# SCH_ESP8266_2025-01-11.net
KiCad netlist of a schematic drawn in EasyEDA
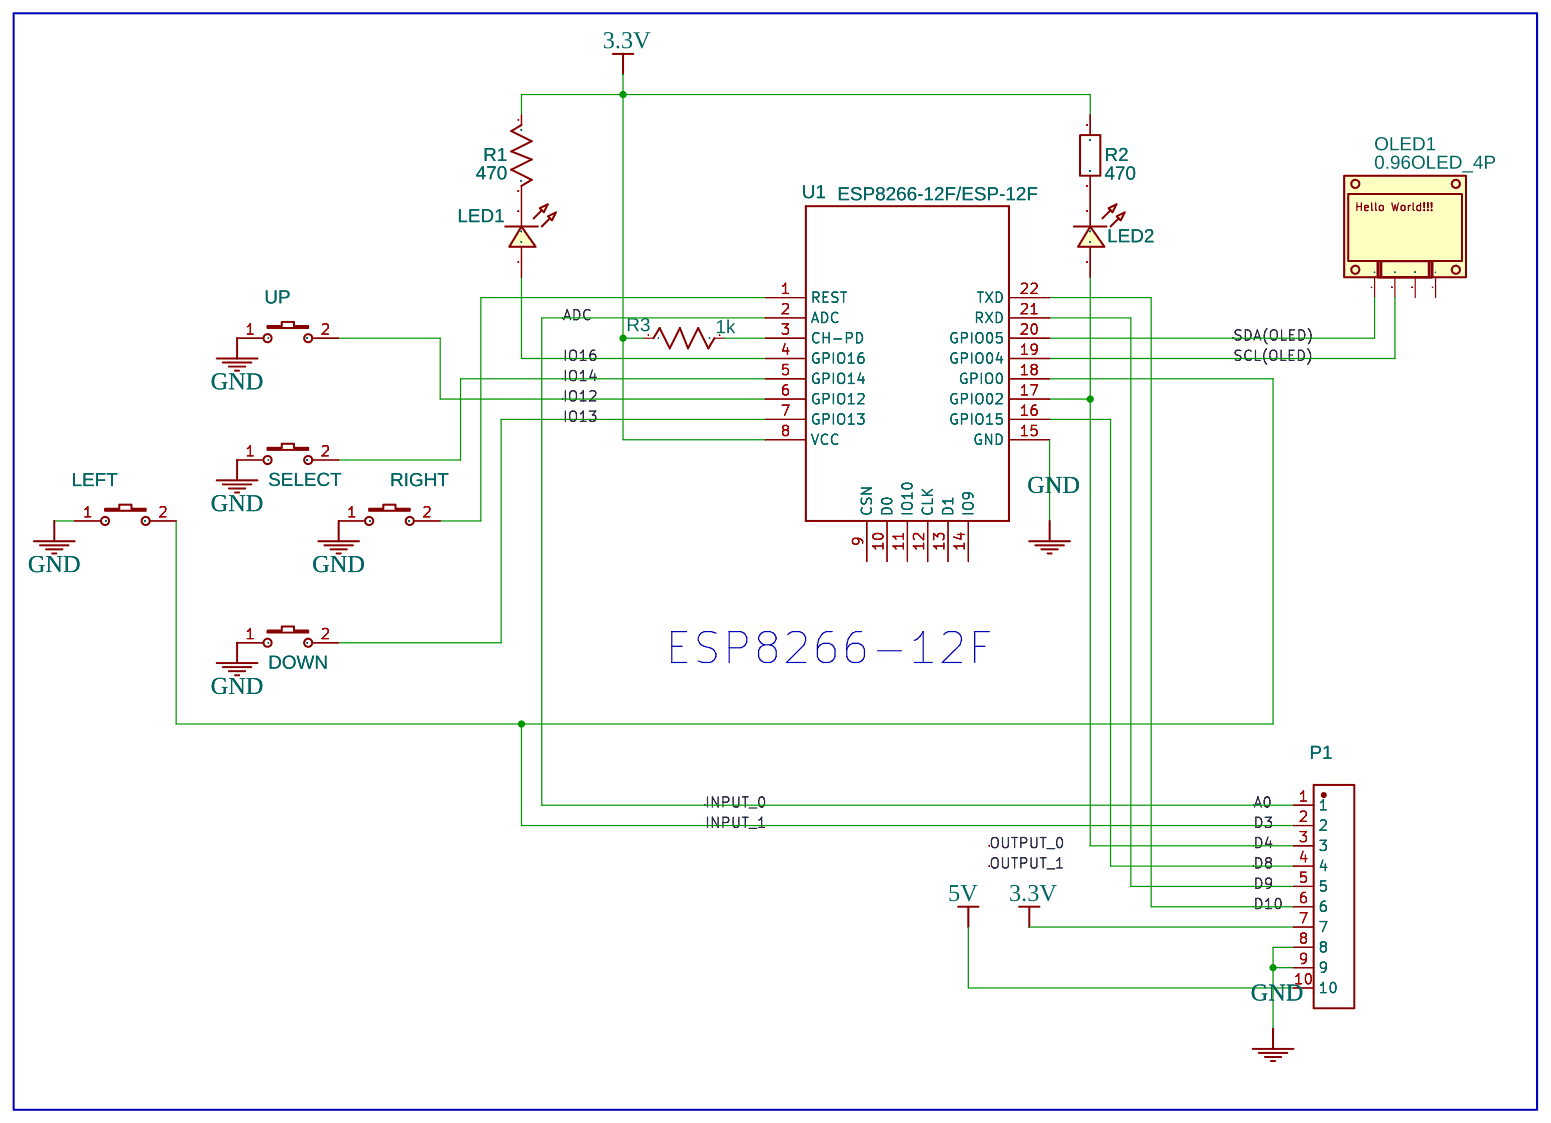
[diagram p0: ESP8266]
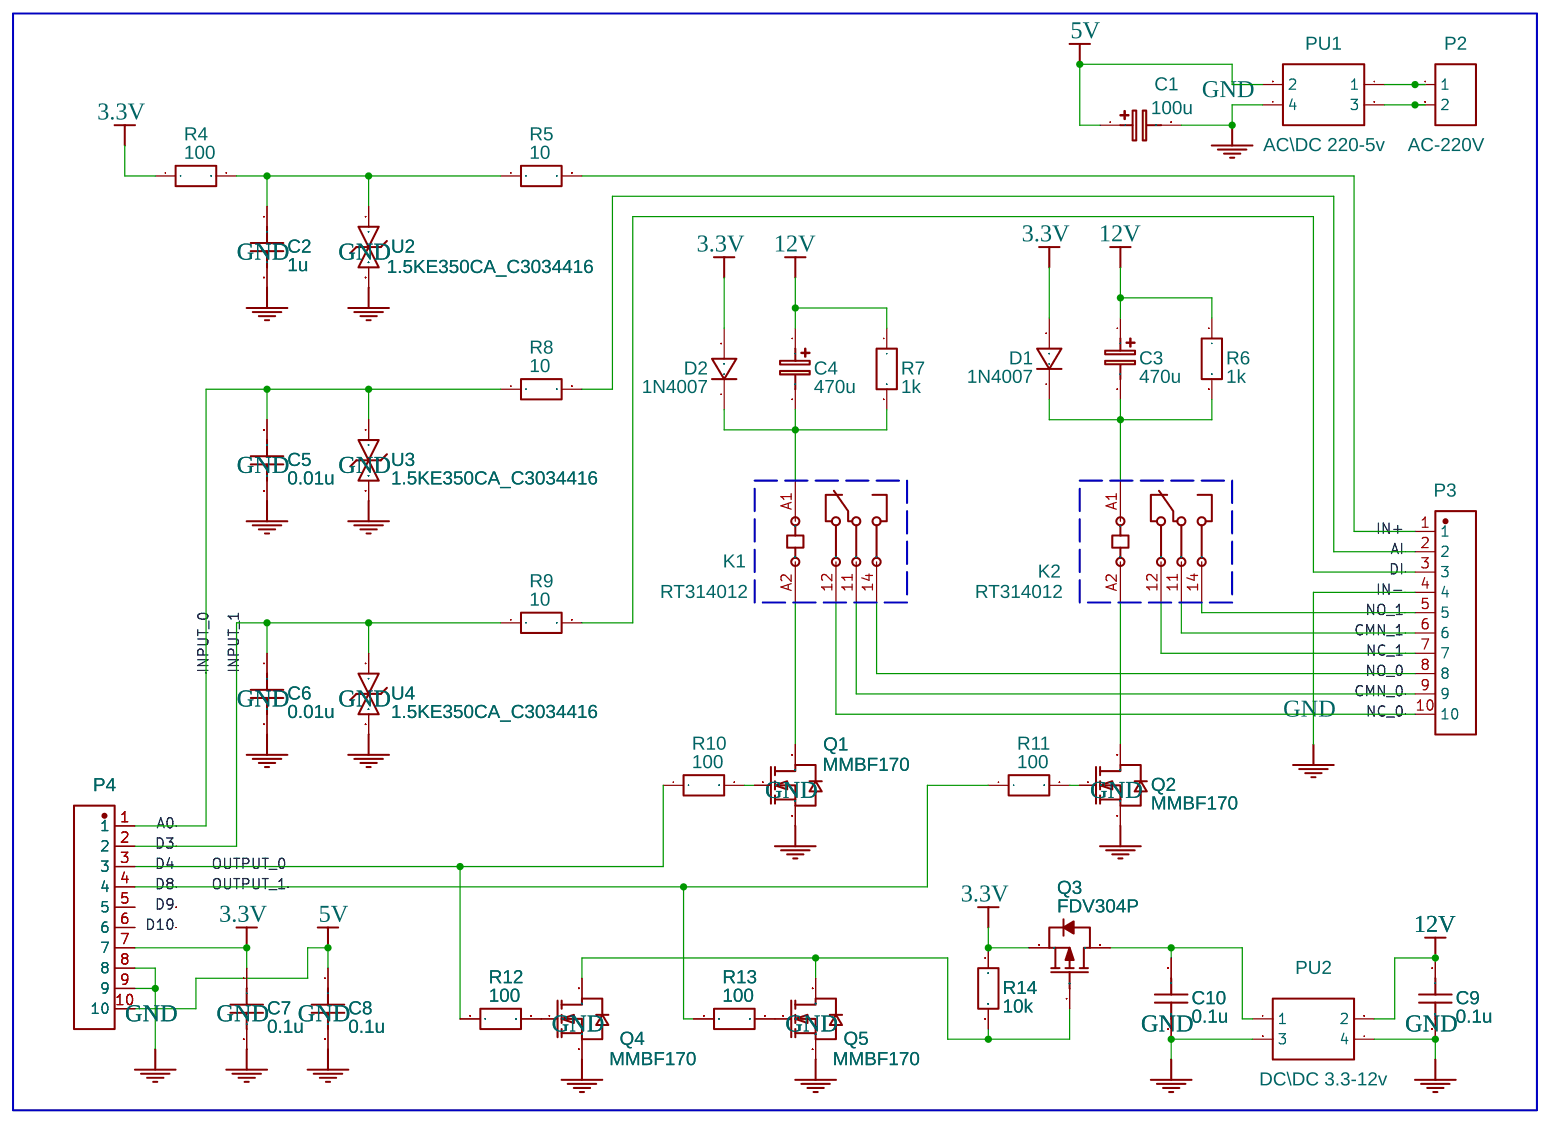
[diagram p1: Peripheral]

(export (version "E")
  (design (tool "Eeschema 10.0.6"))
  (components
    (comp (ref "DOWN")
      (value "K2-3.6×6.1_SMD")
      (fields (field (name "Manufacturer Part") "K2-1107ST-A4SW-06"))
      (libsource (lib "") (part "K2-3.6×6.1_SMD_3"))
    )
    (comp (ref "LED1")
      (value "LED-0603_R")
      (fields
        (field (name "Manufacturer Part") "19-217/R6C-AL1M2VY/3T")
        (field (name "Manufacturer") "EVERLIGHT(台湾亿光)")
      )
      (libsource (lib "") (part "LED-0603_R"))
    )
    (comp (ref "LED2")
      (value "LED-0603_R")
      (fields
        (field (name "Manufacturer Part") "19-217/R6C-AL1M2VY/3T")
        (field (name "Manufacturer") "EVERLIGHT(台湾亿光)")
      )
      (libsource (lib "") (part "LED-0603_R"))
    )
    (comp (ref "LEFT")
      (value "K2-3.6×6.1_SMD")
      (fields (field (name "Manufacturer Part") "K2-1107ST-A4SW-06"))
      (libsource (lib "") (part "K2-3.6×6.1_SMD_1"))
    )
    (comp (ref "OLED1") (value "0.96OLED_4P") (libsource (lib "") (part "0.96OLED_4P")))
    (comp (ref "P1")
      (value "MTP310-1110S1")
      (fields (field (name "Manufacturer") "MINTRON(明硕)"))
      (libsource (lib "") (part "MTP310-1110S1"))
    )
    (comp (ref "R1")
      (value "470")
      (fields (field (name "Manufacturer Part") "?"))
      (libsource (lib "") (part "Resistor"))
    )
    (comp (ref "R2") (value "470") (libsource (lib "") (part "R_0603_EU")))
    (comp (ref "R3")
      (value "1k")
      (fields (field (name "Manufacturer Part") "?"))
      (libsource (lib "") (part "Resistor_1"))
    )
    (comp (ref "RIGHT")
      (value "K2-3.6×6.1_SMD")
      (fields (field (name "Manufacturer Part") "K2-1107ST-A4SW-06"))
      (libsource (lib "") (part "K2-3.6×6.1_SMD_4"))
    )
    (comp (ref "SELECT")
      (value "K2-3.6×6.1_SMD")
      (fields (field (name "Manufacturer Part") "K2-1107ST-A4SW-06"))
      (libsource (lib "") (part "K2-3.6×6.1_SMD"))
    )
    (comp (ref "U1")
      (value "ESP8266-12F/ESP-12F")
      (fields (field (name "Manufacturer Part") "ESP8266-12E/ESP-12E"))
      (libsource (lib "") (part "Unknown_1020_210"))
    )
    (comp (ref "UP")
      (value "K2-3.6×6.1_SMD")
      (fields (field (name "Manufacturer Part") "K2-1107ST-A4SW-06"))
      (libsource (lib "") (part "K2-3.6×6.1_SMD_2"))
    )
    (comp (ref "C1") (value "100u") (libsource (lib "") (part "C_Tan_SMD_A_EU_1")))
    (comp (ref "C2") (value "1u") (libsource (lib "") (part "C_0603_US")))
    (comp (ref "C3") (value "470u") (libsource (lib "") (part "C_Tan_SMD_A_EU")))
    (comp (ref "C4") (value "470u") (libsource (lib "") (part "C_Tan_SMD_A_EU_2")))
    (comp (ref "C5") (value "0.01u") (libsource (lib "") (part "C_0603_US")))
    (comp (ref "C6") (value "0.01u") (libsource (lib "") (part "C_0603_US")))
    (comp (ref "C7") (value "0.1u") (libsource (lib "") (part "C_0603_US")))
    (comp (ref "C8") (value "0.1u") (libsource (lib "") (part "C_0603_US")))
    (comp (ref "C9") (value "0.1u") (libsource (lib "") (part "C_0603_US")))
    (comp (ref "C10") (value "0.1u") (libsource (lib "") (part "C_0603_US_1")))
    (comp (ref "D1")
      (value "1N4007")
      (fields (field (name "Manufacturer") "SEMTECH"))
      (libsource (lib "") (part "1N4007"))
    )
    (comp (ref "D2")
      (value "1N4007")
      (fields (field (name "Manufacturer") "SEMTECH"))
      (libsource (lib "") (part "1N4007"))
    )
    (comp (ref "K1")
      (value "RT314012")
      (fields
        (field (name "Manufacturer Part") "RT314012F")
        (field (name "Manufacturer") "TE Connectivity(美国泰科)")
      )
      (libsource (lib "") (part "RT314012F"))
    )
    (comp (ref "K2")
      (value "RT314012")
      (fields
        (field (name "Manufacturer Part") "RT314012F")
        (field (name "Manufacturer") "TE Connectivity(美国泰科)")
      )
      (libsource (lib "") (part "RT314012F"))
    )
    (comp (ref "P2") (value "AC-220V") (libsource (lib "") (part "CONN-TH_2P-P5.00")))
    (comp (ref "P3")
      (value "MTP310-1110S1")
      (fields (field (name "Manufacturer") "MINTRON(明硕)"))
      (libsource (lib "") (part "MTP310-1110S1_1"))
    )
    (comp (ref "P4")
      (value "MTP310-1110S1")
      (fields (field (name "Manufacturer") "MINTRON(明硕)"))
      (libsource (lib "") (part "MTP310-1110S1"))
    )
    (comp (ref "PU1") (value "AC\\DC 220-5v") (libsource (lib "") (part "HDR-M-2.54_2x2_1")))
    (comp (ref "PU2") (value "DC\\DC 3.3-12v") (libsource (lib "") (part "HDR-M-2.54_2x2")))
    (comp (ref "Q1")
      (value "MMBF170")
      (fields (field (name "Manufacturer Part") "MMBF170Q-13-F") (field (name "Manufacturer") "DIODES(美台)"))
      (libsource (lib "") (part "MMBF170Q-13-F"))
    )
    (comp (ref "Q2")
      (value "MMBF170")
      (fields (field (name "Manufacturer Part") "MMBF170Q-13-F") (field (name "Manufacturer") "DIODES(美台)"))
      (libsource (lib "") (part "MMBF170Q-13-F"))
    )
    (comp (ref "Q3")
      (value "FDV304P")
      (fields (field (name "Manufacturer") "TECH PUBLIC(台舟)"))
      (libsource (lib "") (part "FDV304P_C7419961"))
    )
    (comp (ref "Q4")
      (value "MMBF170")
      (fields (field (name "Manufacturer Part") "MMBF170Q-13-F") (field (name "Manufacturer") "DIODES(美台)"))
      (libsource (lib "") (part "MMBF170Q-13-F"))
    )
    (comp (ref "Q5")
      (value "MMBF170")
      (fields (field (name "Manufacturer Part") "MMBF170Q-13-F") (field (name "Manufacturer") "DIODES(美台)"))
      (libsource (lib "") (part "MMBF170Q-13-F"))
    )
    (comp (ref "R4") (value "100") (libsource (lib "") (part "R_0603_EU_1")))
    (comp (ref "R5") (value "10") (libsource (lib "") (part "R_0603_EU_1")))
    (comp (ref "R6") (value "1k") (libsource (lib "") (part "R_0603_EU")))
    (comp (ref "R7") (value "1k") (libsource (lib "") (part "R_0603_EU")))
    (comp (ref "R8") (value "10") (libsource (lib "") (part "R_0603_EU_1")))
    (comp (ref "R9") (value "10") (libsource (lib "") (part "R_0603_EU_1")))
    (comp (ref "R10") (value "100") (libsource (lib "") (part "R_0603_EU_1")))
    (comp (ref "R11") (value "100") (libsource (lib "") (part "R_0603_EU_1")))
    (comp (ref "R12") (value "100") (libsource (lib "") (part "R_0603_EU_1")))
    (comp (ref "R13") (value "100") (libsource (lib "") (part "R_0603_EU_1")))
    (comp (ref "R14") (value "10k") (libsource (lib "") (part "R_0603_EU")))
    (comp (ref "U2")
      (value "1.5KE350CA_C3034416")
      (fields (field (name "Manufacturer Part") "1.5KE350CA") (field (name "Manufacturer") "Liown(里阳半导体)"))
      (libsource (lib "") (part "1.5KE350CA_C3034416"))
    )
    (comp (ref "U3")
      (value "1.5KE350CA_C3034416")
      (fields (field (name "Manufacturer Part") "1.5KE350CA") (field (name "Manufacturer") "Liown(里阳半导体)"))
      (libsource (lib "") (part "1.5KE350CA_C3034416"))
    )
    (comp (ref "U4")
      (value "1.5KE350CA_C3034416")
      (fields (field (name "Manufacturer Part") "1.5KE350CA") (field (name "Manufacturer") "Liown(里阳半导体)"))
      (libsource (lib "") (part "1.5KE350CA_C3034416"))
    )
  )
  (nets
    (net (code "1") (name "3.3V") (class "Default")
      (node (ref "C7") (pin "1") (pinfunction "1_1") (pintype "unspecified"))
      (node (ref "D1") (pin "2") (pinfunction "2_2") (pintype "unspecified"))
      (node (ref "D2") (pin "2") (pinfunction "2_2") (pintype "unspecified"))
      (node (ref "P1") (pin "7") (pinfunction "7_7") (pintype "unspecified"))
      (node (ref "P4") (pin "7") (pinfunction "7_7") (pintype "unspecified"))
      (node (ref "Q3") (pin "2") (pinfunction "S_2") (pintype "unspecified"))
      (node (ref "R1") (pin "1") (pinfunction "1_1") (pintype "unspecified"))
      (node (ref "R14") (pin "1") (pinfunction "1_1") (pintype "unspecified"))
      (node (ref "R2") (pin "1") (pinfunction "1_1") (pintype "unspecified"))
      (node (ref "R3") (pin "1") (pinfunction "1_1") (pintype "unspecified"))
      (node (ref "R4") (pin "1") (pinfunction "1_1") (pintype "unspecified"))
      (node (ref "U1") (pin "8") (pinfunction "VCC_8") (pintype "unspecified"))
    )
    (net (code "2") (name "5V") (class "Default")
      (node (ref "C1") (pin "1") (pinfunction "1_1") (pintype "unspecified"))
      (node (ref "C8") (pin "1") (pinfunction "1_1") (pintype "unspecified"))
      (node (ref "P1") (pin "10") (pinfunction "10_10") (pintype "unspecified"))
      (node (ref "P4") (pin "10") (pinfunction "10_10") (pintype "unspecified"))
      (node (ref "PU1") (pin "2") (pinfunction "2_2") (pintype "input"))
    )
    (net (code "3") (name "12V") (class "Default")
      (node (ref "C3") (pin "1") (pinfunction "1_1") (pintype "unspecified"))
      (node (ref "C4") (pin "1") (pinfunction "1_1") (pintype "unspecified"))
      (node (ref "C9") (pin "1") (pinfunction "1_1") (pintype "unspecified"))
      (node (ref "PU2") (pin "2") (pinfunction "2_2") (pintype "input"))
      (node (ref "R6") (pin "1") (pinfunction "1_1") (pintype "unspecified"))
      (node (ref "R7") (pin "1") (pinfunction "1_1") (pintype "unspecified"))
    )
    (net (code "4") (name "A0") (class "Default")
      (node (ref "C5") (pin "1") (pinfunction "1_1") (pintype "unspecified"))
      (node (ref "P1") (pin "1") (pinfunction "1_1") (pintype "unspecified"))
      (node (ref "P4") (pin "1") (pinfunction "1_1") (pintype "unspecified"))
      (node (ref "R8") (pin "1") (pinfunction "1_1") (pintype "unspecified"))
      (node (ref "U1") (pin "2") (pinfunction "ADC_2") (pintype "unspecified"))
      (node (ref "U3") (pin "1") (pinfunction "1_1") (pintype "unspecified"))
    )
    (net (code "5") (name "AI") (class "Default")
      (node (ref "P3") (pin "2") (pinfunction "2_2") (pintype "unspecified"))
      (node (ref "R8") (pin "2") (pinfunction "2_2") (pintype "unspecified"))
    )
    (net (code "6") (name "CMN_0") (class "Default")
      (node (ref "K1") (pin "11") (pinfunction "11_11") (pintype "unspecified"))
      (node (ref "P3") (pin "9") (pinfunction "9_9") (pintype "unspecified"))
    )
    (net (code "7") (name "CMN_1") (class "Default")
      (node (ref "K2") (pin "11") (pinfunction "11_11") (pintype "unspecified"))
      (node (ref "P3") (pin "6") (pinfunction "6_6") (pintype "unspecified"))
    )
    (net (code "8") (name "D3") (class "Default")
      (node (ref "C6") (pin "1") (pinfunction "1_1") (pintype "unspecified"))
      (node (ref "LEFT") (pin "2") (pinfunction "2_2") (pintype "unspecified"))
      (node (ref "P1") (pin "2") (pinfunction "2_2") (pintype "unspecified"))
      (node (ref "P4") (pin "2") (pinfunction "2_2") (pintype "unspecified"))
      (node (ref "R9") (pin "1") (pinfunction "1_1") (pintype "unspecified"))
      (node (ref "U1") (pin "18") (pinfunction "GPIO0_18") (pintype "unspecified"))
      (node (ref "U4") (pin "1") (pinfunction "1_1") (pintype "unspecified"))
    )
    (net (code "9") (name "D4") (class "Default")
      (node (ref "LED2") (pin "1") (pinfunction "1_1") (pintype "unspecified"))
      (node (ref "P1") (pin "3") (pinfunction "3_3") (pintype "unspecified"))
      (node (ref "P4") (pin "3") (pinfunction "3_3") (pintype "unspecified"))
      (node (ref "R10") (pin "1") (pinfunction "1_1") (pintype "unspecified"))
      (node (ref "R12") (pin "1") (pinfunction "1_1") (pintype "unspecified"))
      (node (ref "U1") (pin "17") (pinfunction "GPIO02_17") (pintype "unspecified"))
    )
    (net (code "10") (name "D8") (class "Default")
      (node (ref "P1") (pin "4") (pinfunction "4_4") (pintype "unspecified"))
      (node (ref "P4") (pin "4") (pinfunction "4_4") (pintype "unspecified"))
      (node (ref "R11") (pin "1") (pinfunction "1_1") (pintype "unspecified"))
      (node (ref "R13") (pin "1") (pinfunction "1_1") (pintype "unspecified"))
      (node (ref "U1") (pin "16") (pinfunction "GPIO15_16") (pintype "unspecified"))
    )
    (net (code "11") (name "D9") (class "Default")
      (node (ref "P1") (pin "5") (pinfunction "5_5") (pintype "unspecified"))
      (node (ref "U1") (pin "21") (pinfunction "RXD_21") (pintype "unspecified"))
    )
    (net (code "12") (name "D10") (class "Default")
      (node (ref "P1") (pin "6") (pinfunction "6_6") (pintype "unspecified"))
      (node (ref "U1") (pin "22") (pinfunction "TXD_22") (pintype "unspecified"))
    )
    (net (code "13") (name "DI") (class "Default")
      (node (ref "P3") (pin "3") (pinfunction "3_3") (pintype "unspecified"))
      (node (ref "R9") (pin "2") (pinfunction "2_2") (pintype "unspecified"))
    )
    (net (code "14") (name "IN+") (class "Default")
      (node (ref "P3") (pin "1") (pinfunction "1_1") (pintype "unspecified"))
      (node (ref "R5") (pin "2") (pinfunction "2_2") (pintype "unspecified"))
    )
    (net (code "15") (name "IN-") (class "Default")
      (node (ref "C1") (pin "2") (pinfunction "2_2") (pintype "unspecified"))
      (node (ref "C10") (pin "1") (pinfunction "1_1") (pintype "unspecified"))
      (node (ref "C2") (pin "2") (pinfunction "2_2") (pintype "unspecified"))
      (node (ref "C5") (pin "2") (pinfunction "2_2") (pintype "unspecified"))
      (node (ref "C6") (pin "2") (pinfunction "2_2") (pintype "unspecified"))
      (node (ref "C7") (pin "2") (pinfunction "2_2") (pintype "unspecified"))
      (node (ref "C8") (pin "2") (pinfunction "2_2") (pintype "unspecified"))
      (node (ref "C9") (pin "2") (pinfunction "2_2") (pintype "unspecified"))
      (node (ref "DOWN") (pin "1") (pinfunction "1_1") (pintype "unspecified"))
      (node (ref "LEFT") (pin "1") (pinfunction "1_1") (pintype "unspecified"))
      (node (ref "P1") (pin "8") (pinfunction "8_8") (pintype "unspecified"))
      (node (ref "P1") (pin "9") (pinfunction "9_9") (pintype "unspecified"))
      (node (ref "P3") (pin "4") (pinfunction "4_4") (pintype "unspecified"))
      (node (ref "P4") (pin "8") (pinfunction "8_8") (pintype "unspecified"))
      (node (ref "P4") (pin "9") (pinfunction "9_9") (pintype "unspecified"))
      (node (ref "PU1") (pin "4") (pinfunction "4_4") (pintype "input"))
      (node (ref "PU2") (pin "3") (pinfunction "3_3") (pintype "input"))
      (node (ref "PU2") (pin "4") (pinfunction "4_4") (pintype "input"))
      (node (ref "Q1") (pin "2") (pinfunction "S_2") (pintype "unspecified"))
      (node (ref "Q2") (pin "2") (pinfunction "S_2") (pintype "unspecified"))
      (node (ref "Q4") (pin "2") (pinfunction "S_2") (pintype "unspecified"))
      (node (ref "Q5") (pin "2") (pinfunction "S_2") (pintype "unspecified"))
      (node (ref "RIGHT") (pin "1") (pinfunction "1_1") (pintype "unspecified"))
      (node (ref "SELECT") (pin "1") (pinfunction "1_1") (pintype "unspecified"))
      (node (ref "U1") (pin "15") (pinfunction "GND_15") (pintype "unspecified"))
      (node (ref "U2") (pin "2") (pinfunction "2_2") (pintype "unspecified"))
      (node (ref "U3") (pin "2") (pinfunction "2_2") (pintype "unspecified"))
      (node (ref "U4") (pin "2") (pinfunction "2_2") (pintype "unspecified"))
      (node (ref "UP") (pin "1") (pinfunction "1_1") (pintype "unspecified"))
    )
    (net (code "16") (name "IO12") (class "Default")
      (node (ref "U1") (pin "6") (pinfunction "GPIO12_6") (pintype "unspecified"))
      (node (ref "UP") (pin "2") (pinfunction "2_2") (pintype "unspecified"))
    )
    (net (code "17") (name "IO13") (class "Default")
      (node (ref "DOWN") (pin "2") (pinfunction "2_2") (pintype "unspecified"))
      (node (ref "U1") (pin "7") (pinfunction "GPIO13_7") (pintype "unspecified"))
    )
    (net (code "18") (name "IO14") (class "Default")
      (node (ref "SELECT") (pin "2") (pinfunction "2_2") (pintype "unspecified"))
      (node (ref "U1") (pin "5") (pinfunction "GPIO14_5") (pintype "unspecified"))
    )
    (net (code "19") (name "IO16") (class "Default")
      (node (ref "LED1") (pin "1") (pinfunction "1_1") (pintype "unspecified"))
      (node (ref "U1") (pin "4") (pinfunction "GPIO16_4") (pintype "unspecified"))
    )
    (net (code "20") (name "NC_0") (class "Default")
      (node (ref "K1") (pin "12") (pinfunction "12_12") (pintype "unspecified"))
      (node (ref "P3") (pin "10") (pinfunction "10_10") (pintype "unspecified"))
    )
    (net (code "21") (name "NC_1") (class "Default")
      (node (ref "K2") (pin "12") (pinfunction "12_12") (pintype "unspecified"))
      (node (ref "P3") (pin "7") (pinfunction "7_7") (pintype "unspecified"))
    )
    (net (code "22") (name "NO_0") (class "Default")
      (node (ref "K1") (pin "14") (pinfunction "14_14") (pintype "unspecified"))
      (node (ref "P3") (pin "8") (pinfunction "8_8") (pintype "unspecified"))
    )
    (net (code "23") (name "NO_1") (class "Default")
      (node (ref "K2") (pin "14") (pinfunction "14_14") (pintype "unspecified"))
      (node (ref "P3") (pin "5") (pinfunction "5_5") (pintype "unspecified"))
    )
    (net (code "24") (name "Net-(C2-Pad1)") (class "Default")
      (node (ref "C2") (pin "1") (pinfunction "1_1") (pintype "unspecified"))
      (node (ref "R4") (pin "2") (pinfunction "2_2") (pintype "unspecified"))
      (node (ref "R5") (pin "1") (pinfunction "1_1") (pintype "unspecified"))
      (node (ref "U2") (pin "1") (pinfunction "1_1") (pintype "unspecified"))
    )
    (net (code "25") (name "Net-(C3-Pad2)") (class "Default")
      (node (ref "C3") (pin "2") (pinfunction "2_2") (pintype "unspecified"))
      (node (ref "D1") (pin "1") (pinfunction "1_1") (pintype "unspecified"))
      (node (ref "K2") (pin "A1") (pinfunction "A1_A1") (pintype "unspecified"))
      (node (ref "R6") (pin "2") (pinfunction "2_2") (pintype "unspecified"))
    )
    (net (code "26") (name "Net-(C4-Pad2)") (class "Default")
      (node (ref "C4") (pin "2") (pinfunction "2_2") (pintype "unspecified"))
      (node (ref "D2") (pin "1") (pinfunction "1_1") (pintype "unspecified"))
      (node (ref "K1") (pin "A1") (pinfunction "A1_A1") (pintype "unspecified"))
      (node (ref "R7") (pin "2") (pinfunction "2_2") (pintype "unspecified"))
    )
    (net (code "27") (name "Net-(LED1-Pad2)") (class "Default")
      (node (ref "LED1") (pin "2") (pinfunction "2_2") (pintype "unspecified"))
      (node (ref "R1") (pin "2") (pinfunction "2_2") (pintype "unspecified"))
    )
    (net (code "28") (name "Net-(LED2-Pad2)") (class "Default")
      (node (ref "LED2") (pin "2") (pinfunction "2_2") (pintype "unspecified"))
      (node (ref "R2") (pin "2") (pinfunction "2_2") (pintype "unspecified"))
    )
    (net (code "29") (name "Net-(P2-Pad1)") (class "Default")
      (node (ref "P2") (pin "1") (pinfunction "1_1") (pintype "unspecified"))
      (node (ref "PU1") (pin "1") (pinfunction "1_1") (pintype "input"))
    )
    (net (code "30") (name "Net-(P2-Pad2)") (class "Default")
      (node (ref "P2") (pin "2") (pinfunction "2_2") (pintype "unspecified"))
      (node (ref "PU1") (pin "3") (pinfunction "3_3") (pintype "input"))
    )
    (net (code "31") (name "Net-(Q1-D)") (class "Default")
      (node (ref "K1") (pin "A2") (pinfunction "A2_A2") (pintype "unspecified"))
      (node (ref "Q1") (pin "3") (pinfunction "D_3") (pintype "unspecified"))
    )
    (net (code "32") (name "Net-(Q1-G)") (class "Default")
      (node (ref "Q1") (pin "1") (pinfunction "G_1") (pintype "unspecified"))
      (node (ref "R10") (pin "2") (pinfunction "2_2") (pintype "unspecified"))
    )
    (net (code "33") (name "Net-(Q2-D)") (class "Default")
      (node (ref "K2") (pin "A2") (pinfunction "A2_A2") (pintype "unspecified"))
      (node (ref "Q2") (pin "3") (pinfunction "D_3") (pintype "unspecified"))
    )
    (net (code "34") (name "Net-(Q2-G)") (class "Default")
      (node (ref "Q2") (pin "1") (pinfunction "G_1") (pintype "unspecified"))
      (node (ref "R11") (pin "2") (pinfunction "2_2") (pintype "unspecified"))
    )
    (net (code "35") (name "Net-(Q3-D)") (class "Default")
      (node (ref "C10") (pin "2") (pinfunction "2_2") (pintype "unspecified"))
      (node (ref "PU2") (pin "1") (pinfunction "1_1") (pintype "input"))
      (node (ref "Q3") (pin "3") (pinfunction "D_3") (pintype "unspecified"))
    )
    (net (code "36") (name "Net-(Q3-G)") (class "Default")
      (node (ref "Q3") (pin "1") (pinfunction "G_1") (pintype "unspecified"))
      (node (ref "Q4") (pin "3") (pinfunction "D_3") (pintype "unspecified"))
      (node (ref "Q5") (pin "3") (pinfunction "D_3") (pintype "unspecified"))
      (node (ref "R14") (pin "2") (pinfunction "2_2") (pintype "unspecified"))
    )
    (net (code "37") (name "Net-(Q4-G)") (class "Default")
      (node (ref "Q4") (pin "1") (pinfunction "G_1") (pintype "unspecified"))
      (node (ref "R12") (pin "2") (pinfunction "2_2") (pintype "unspecified"))
    )
    (net (code "38") (name "Net-(Q5-G)") (class "Default")
      (node (ref "Q5") (pin "1") (pinfunction "G_1") (pintype "unspecified"))
      (node (ref "R13") (pin "2") (pinfunction "2_2") (pintype "unspecified"))
    )
    (net (code "39") (name "Net-(U1-CH-PD)") (class "Default")
      (node (ref "R3") (pin "2") (pinfunction "2_2") (pintype "unspecified"))
      (node (ref "U1") (pin "3") (pinfunction "CH-PD_3") (pintype "unspecified"))
    )
    (net (code "40") (name "Net-(U1-REST)") (class "Default")
      (node (ref "RIGHT") (pin "2") (pinfunction "2_2") (pintype "unspecified"))
      (node (ref "U1") (pin "1") (pinfunction "REST_1") (pintype "unspecified"))
    )
    (net (code "41") (name "SCL(OLED)") (class "Default")
      (node (ref "OLED1") (pin "2") (pinfunction "2_2") (pintype "unspecified"))
      (node (ref "U1") (pin "19") (pinfunction "GPIO04_19") (pintype "unspecified"))
    )
    (net (code "42") (name "SDA(OLED)") (class "Default")
      (node (ref "OLED1") (pin "1") (pinfunction "1_1") (pintype "unspecified"))
      (node (ref "U1") (pin "20") (pinfunction "GPIO05_20") (pintype "unspecified"))
    )
    (net (code "43") (name "unconnected-(OLED1-Pad3)") (class "Default")
      (node (ref "OLED1") (pin "3") (pinfunction "3_3") (pintype "unspecified"))
    )
    (net (code "44") (name "unconnected-(OLED1-Pad4)") (class "Default")
      (node (ref "OLED1") (pin "4") (pinfunction "4_4") (pintype "unspecified"))
    )
    (net (code "45") (name "unconnected-(P4-Pad5)") (class "Default")
      (node (ref "P4") (pin "5") (pinfunction "5_5") (pintype "unspecified"))
    )
    (net (code "46") (name "unconnected-(P4-Pad6)") (class "Default")
      (node (ref "P4") (pin "6") (pinfunction "6_6") (pintype "unspecified"))
    )
    (net (code "47") (name "unconnected-(U1-CLK-Pad12)") (class "Default")
      (node (ref "U1") (pin "12") (pinfunction "CLK_12") (pintype "unspecified"))
    )
    (net (code "48") (name "unconnected-(U1-CSN-Pad9)") (class "Default")
      (node (ref "U1") (pin "9") (pinfunction "CSN_9") (pintype "unspecified"))
    )
    (net (code "49") (name "unconnected-(U1-D0-Pad10)") (class "Default")
      (node (ref "U1") (pin "10") (pinfunction "D0_10") (pintype "unspecified"))
    )
    (net (code "50") (name "unconnected-(U1-D1-Pad13)") (class "Default")
      (node (ref "U1") (pin "13") (pinfunction "D1_13") (pintype "unspecified"))
    )
    (net (code "51") (name "unconnected-(U1-IO9-Pad14)") (class "Default")
      (node (ref "U1") (pin "14") (pinfunction "IO9_14") (pintype "unspecified"))
    )
    (net (code "52") (name "unconnected-(U1-IO10-Pad11)") (class "Default")
      (node (ref "U1") (pin "11") (pinfunction "IO10_11") (pintype "unspecified"))
    )
  )
)
